# Can-Shield.net
KiCad netlist of a schematic drawn in Altium Designer
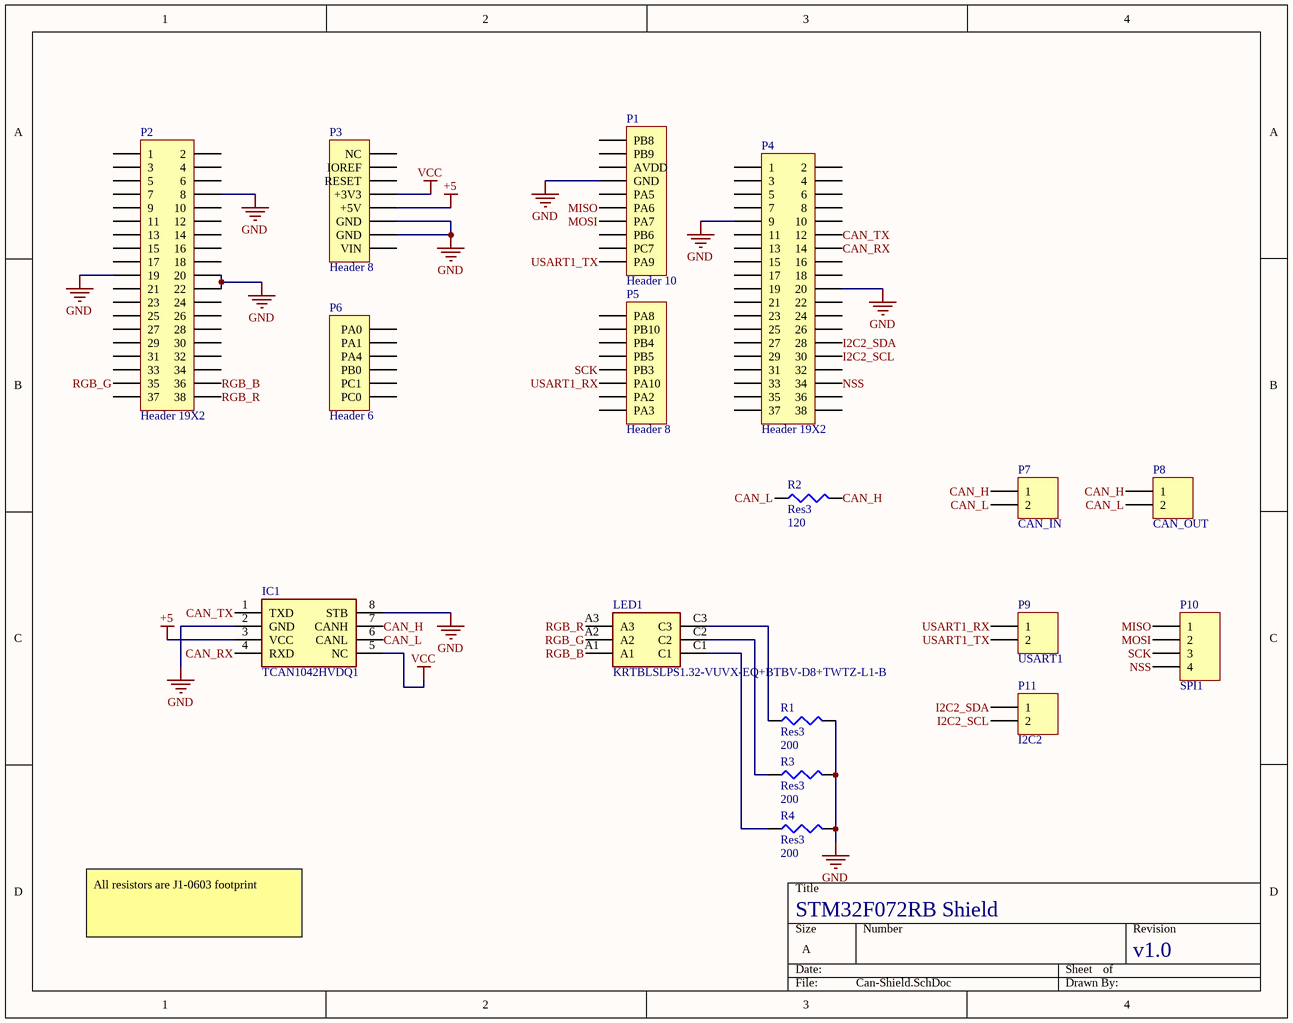
[diagram p0: Can-Shield.SchDoc]

(export (version "E")
  (design (tool "Eeschema 10.0.6"))
  (components
    (comp (ref "IC1")
      (value "TCAN1042HVDQ1")
      (footprint "SamacSys:SOIC127P600X175-8N")
      (description "Integrated Circuit")
      (fields (field (name "MOUSER PART NUMBER") "595-TCAN1042HVDQ1"))
      (libsource (lib "*") (part "TCAN1042HVDQ1"))
    )
    (comp (ref "LED1")
      (value "KRTBLSLPS1.32-VUVX-EQ+BTBV-D8+TWTZ-L1-B")
      (footprint "SamacSys:KRTBLSLPS132VUVXEQBTBVD8TWTZL1B")
      (description "LED")
      (fields (field (name "MOUSER PART NUMBER") "720-KRTBLSLPS13A0062"))
      (libsource (lib "*") (part "KRTBLSLPS1.32-VUVX-EQ+BTBV-D8+TWTZ-L1-B"))
    )
    (comp (ref "P1")
      (value "Header 10")
      (footprint "HDR1X10")
      (description "Header, 10-Pin")
      (fields (field (name "PUBLISHER") "Altium Limited"))
      (libsource (lib "Miscellaneous Connectors") (part "Header 10"))
    )
    (comp (ref "P2")
      (value "Header 19X2")
      (footprint "HDR2X19")
      (description "Header, 19-Pin, Dual row")
      (fields (field (name "PUBLISHER") "Altium Limited"))
      (libsource (lib "Miscellaneous Connectors") (part "Header 19X2"))
    )
    (comp (ref "P3")
      (value "Header 8")
      (footprint "HDR1X8")
      (description "Header, 8-Pin")
      (fields (field (name "PUBLISHER") "Altium Limited"))
      (libsource (lib "") (part "Header 8_1"))
    )
    (comp (ref "P4")
      (value "Header 19X2")
      (footprint "HDR2X19")
      (description "Header, 19-Pin, Dual row")
      (fields (field (name "PUBLISHER") "Altium Limited"))
      (libsource (lib "Miscellaneous Connectors") (part "Header 19X2"))
    )
    (comp (ref "P5")
      (value "Header 8")
      (footprint "HDR1X8")
      (description "Header, 8-Pin")
      (fields (field (name "PUBLISHER") "Altium Limited"))
      (libsource (lib "Miscellaneous Connectors") (part "Header 8"))
    )
    (comp (ref "P6")
      (value "Header 6")
      (footprint "HDR1X6")
      (description "Header, 6-Pin")
      (fields (field (name "PUBLISHER") "Altium Limited"))
      (libsource (lib "Miscellaneous Connectors") (part "Header 6"))
    )
    (comp (ref "P7")
      (value "CAN_IN")
      (footprint "HDR1X2")
      (description "Header, 2-Pin")
      (fields (field (name "PUBLISHER") "Altium Limited"))
      (libsource (lib "Miscellaneous Connectors") (part "Header 2"))
    )
    (comp (ref "P8")
      (value "CAN_OUT")
      (footprint "HDR1X2")
      (description "Header, 2-Pin")
      (fields (field (name "PUBLISHER") "Altium Limited"))
      (libsource (lib "Miscellaneous Connectors") (part "Header 2"))
    )
    (comp (ref "P9")
      (value "USART1")
      (footprint "HDR1X2")
      (description "Header, 2-Pin")
      (fields (field (name "PUBLISHER") "Altium Limited"))
      (libsource (lib "Miscellaneous Connectors") (part "Header 2"))
    )
    (comp (ref "P10")
      (value "SPI1")
      (footprint "HDR1X4")
      (description "Header, 4-Pin")
      (fields (field (name "PUBLISHER") "Altium Limited"))
      (libsource (lib "Miscellaneous Connectors") (part "Header 4"))
    )
    (comp (ref "P11")
      (value "I2C2")
      (footprint "HDR1X2")
      (description "Header, 2-Pin")
      (fields (field (name "PUBLISHER") "Altium Limited"))
      (libsource (lib "Miscellaneous Connectors") (part "Header 2"))
    )
    (comp (ref "R1")
      (value "Res3")
      (footprint "J1-0603")
      (description "Resistor")
      (fields (field (name "ALTIUM_VALUE") "200") (field (name "PUBLISHER") "Altium Limited"))
      (libsource (lib "Miscellaneous Devices") (part "Res3"))
    )
    (comp (ref "R2")
      (value "Res3")
      (footprint "J1-0603")
      (description "Resistor")
      (fields (field (name "ALTIUM_VALUE") "120") (field (name "PUBLISHER") "Altium Limited"))
      (libsource (lib "Miscellaneous Devices") (part "Res3"))
    )
    (comp (ref "R3")
      (value "Res3")
      (footprint "J1-0603")
      (description "Resistor")
      (fields (field (name "ALTIUM_VALUE") "200") (field (name "PUBLISHER") "Altium Limited"))
      (libsource (lib "Miscellaneous Devices") (part "Res3"))
    )
    (comp (ref "R4")
      (value "Res3")
      (footprint "J1-0603")
      (description "Resistor")
      (fields (field (name "ALTIUM_VALUE") "200") (field (name "PUBLISHER") "Altium Limited"))
      (libsource (lib "Miscellaneous Devices") (part "Res3"))
    )
  )
  (nets
    (net (code "1") (name "+5") (class "Default")
      (node (ref "IC1") (pin "3") (pinfunction "VCC_3") (pintype "passive"))
      (node (ref "P3") (pin "5") (pinfunction "+5V_5") (pintype "passive"))
    )
    (net (code "2") (name "/CAN_H") (class "Default")
      (node (ref "IC1") (pin "7") (pinfunction "CANH_7") (pintype "passive"))
      (node (ref "P7") (pin "1") (pinfunction "1_1") (pintype "passive"))
      (node (ref "P8") (pin "1") (pinfunction "1_1") (pintype "passive"))
      (node (ref "R2") (pin "2") (pinfunction "2_2") (pintype "passive"))
    )
    (net (code "3") (name "/CAN_L") (class "Default")
      (node (ref "IC1") (pin "6") (pinfunction "CANL_6") (pintype "passive"))
      (node (ref "P7") (pin "2") (pinfunction "2_2") (pintype "passive"))
      (node (ref "P8") (pin "2") (pinfunction "2_2") (pintype "passive"))
      (node (ref "R2") (pin "1") (pinfunction "1_1") (pintype "passive"))
    )
    (net (code "4") (name "/CAN_RX") (class "Default")
      (node (ref "IC1") (pin "4") (pinfunction "RXD_4") (pintype "passive"))
      (node (ref "P4") (pin "14") (pinfunction "14_14") (pintype "passive"))
    )
    (net (code "5") (name "/CAN_TX") (class "Default")
      (node (ref "IC1") (pin "1") (pinfunction "TXD_1") (pintype "passive"))
      (node (ref "P4") (pin "12") (pinfunction "12_12") (pintype "passive"))
    )
    (net (code "6") (name "/I2C2_SCL") (class "Default")
      (node (ref "P11") (pin "2") (pinfunction "2_2") (pintype "passive"))
      (node (ref "P4") (pin "30") (pinfunction "30_30") (pintype "passive"))
    )
    (net (code "7") (name "/I2C2_SDA") (class "Default")
      (node (ref "P11") (pin "1") (pinfunction "1_1") (pintype "passive"))
      (node (ref "P4") (pin "28") (pinfunction "28_28") (pintype "passive"))
    )
    (net (code "8") (name "/MISO") (class "Default")
      (node (ref "P1") (pin "6") (pinfunction "PA6_6") (pintype "passive"))
      (node (ref "P10") (pin "1") (pinfunction "1_1") (pintype "passive"))
    )
    (net (code "9") (name "/MOSI") (class "Default")
      (node (ref "P1") (pin "7") (pinfunction "PA7_7") (pintype "passive"))
      (node (ref "P10") (pin "2") (pinfunction "2_2") (pintype "passive"))
    )
    (net (code "10") (name "/NSS") (class "Default")
      (node (ref "P10") (pin "4") (pinfunction "4_4") (pintype "passive"))
      (node (ref "P4") (pin "34") (pinfunction "34_34") (pintype "passive"))
    )
    (net (code "11") (name "/RGB_B") (class "Default")
      (node (ref "LED1") (pin "A1") (pinfunction "A1_A1") (pintype "passive"))
      (node (ref "P2") (pin "36") (pinfunction "36_36") (pintype "passive"))
    )
    (net (code "12") (name "/RGB_G") (class "Default")
      (node (ref "LED1") (pin "A2") (pinfunction "A2_A2") (pintype "passive"))
      (node (ref "P2") (pin "35") (pinfunction "35_35") (pintype "passive"))
    )
    (net (code "13") (name "/RGB_R") (class "Default")
      (node (ref "LED1") (pin "A3") (pinfunction "A3_A3") (pintype "passive"))
      (node (ref "P2") (pin "38") (pinfunction "38_38") (pintype "passive"))
    )
    (net (code "14") (name "/SCK") (class "Default")
      (node (ref "P10") (pin "3") (pinfunction "3_3") (pintype "passive"))
      (node (ref "P5") (pin "5") (pinfunction "PB3_5") (pintype "passive"))
    )
    (net (code "15") (name "/USART1_RX") (class "Default")
      (node (ref "P5") (pin "6") (pinfunction "PA10_6") (pintype "passive"))
      (node (ref "P9") (pin "1") (pinfunction "1_1") (pintype "passive"))
    )
    (net (code "16") (name "/USART1_TX") (class "Default")
      (node (ref "P1") (pin "10") (pinfunction "PA9_10") (pintype "passive"))
      (node (ref "P9") (pin "2") (pinfunction "2_2") (pintype "passive"))
    )
    (net (code "17") (name "GND") (class "Default")
      (node (ref "IC1") (pin "2") (pinfunction "GND_2") (pintype "passive"))
      (node (ref "IC1") (pin "8") (pinfunction "STB_8") (pintype "passive"))
      (node (ref "P1") (pin "4") (pinfunction "GND_4") (pintype "passive"))
      (node (ref "P2") (pin "19") (pinfunction "19_19") (pintype "passive"))
      (node (ref "P2") (pin "20") (pinfunction "20_20") (pintype "passive"))
      (node (ref "P2") (pin "22") (pinfunction "22_22") (pintype "passive"))
      (node (ref "P2") (pin "8") (pinfunction "8_8") (pintype "passive"))
      (node (ref "P3") (pin "6") (pinfunction "GND_6") (pintype "passive"))
      (node (ref "P3") (pin "7") (pinfunction "GND_7") (pintype "passive"))
      (node (ref "P4") (pin "20") (pinfunction "20_20") (pintype "passive"))
      (node (ref "P4") (pin "9") (pinfunction "9_9") (pintype "passive"))
      (node (ref "R1") (pin "2") (pinfunction "2_2") (pintype "passive"))
      (node (ref "R3") (pin "2") (pinfunction "2_2") (pintype "passive"))
      (node (ref "R4") (pin "2") (pinfunction "2_2") (pintype "passive"))
    )
    (net (code "18") (name "Net-(LED1-PadC1)") (class "Default")
      (node (ref "LED1") (pin "C1") (pinfunction "C1_C1") (pintype "passive"))
      (node (ref "R4") (pin "1") (pinfunction "1_1") (pintype "passive"))
    )
    (net (code "19") (name "Net-(LED1-PadC2)") (class "Default")
      (node (ref "LED1") (pin "C2") (pinfunction "C2_C2") (pintype "passive"))
      (node (ref "R3") (pin "1") (pinfunction "1_1") (pintype "passive"))
    )
    (net (code "20") (name "Net-(LED1-PadC3)") (class "Default")
      (node (ref "LED1") (pin "C3") (pinfunction "C3_C3") (pintype "passive"))
      (node (ref "R1") (pin "1") (pinfunction "1_1") (pintype "passive"))
    )
    (net (code "21") (name "VCC") (class "Default")
      (node (ref "IC1") (pin "5") (pinfunction "NC_5") (pintype "passive"))
      (node (ref "P3") (pin "4") (pinfunction "+3V3_4") (pintype "passive"))
    )
    (net (code "22") (name "unconnected-(P1-AVDD-Pad3)") (class "Default")
      (node (ref "P1") (pin "3") (pinfunction "AVDD_3") (pintype "passive"))
    )
    (net (code "23") (name "unconnected-(P1-PA5-Pad5)") (class "Default")
      (node (ref "P1") (pin "5") (pinfunction "PA5_5") (pintype "passive"))
    )
    (net (code "24") (name "unconnected-(P1-PB6-Pad8)") (class "Default")
      (node (ref "P1") (pin "8") (pinfunction "PB6_8") (pintype "passive"))
    )
    (net (code "25") (name "unconnected-(P1-PB8-Pad1)") (class "Default")
      (node (ref "P1") (pin "1") (pinfunction "PB8_1") (pintype "passive"))
    )
    (net (code "26") (name "unconnected-(P1-PB9-Pad2)") (class "Default")
      (node (ref "P1") (pin "2") (pinfunction "PB9_2") (pintype "passive"))
    )
    (net (code "27") (name "unconnected-(P1-PC7-Pad9)") (class "Default")
      (node (ref "P1") (pin "9") (pinfunction "PC7_9") (pintype "passive"))
    )
    (net (code "28") (name "unconnected-(P2-Pad1)") (class "Default")
      (node (ref "P2") (pin "1") (pinfunction "1_1") (pintype "passive"))
    )
    (net (code "29") (name "unconnected-(P2-Pad2)") (class "Default")
      (node (ref "P2") (pin "2") (pinfunction "2_2") (pintype "passive"))
    )
    (net (code "30") (name "unconnected-(P2-Pad3)") (class "Default")
      (node (ref "P2") (pin "3") (pinfunction "3_3") (pintype "passive"))
    )
    (net (code "31") (name "unconnected-(P2-Pad4)") (class "Default")
      (node (ref "P2") (pin "4") (pinfunction "4_4") (pintype "passive"))
    )
    (net (code "32") (name "unconnected-(P2-Pad5)") (class "Default")
      (node (ref "P2") (pin "5") (pinfunction "5_5") (pintype "passive"))
    )
    (net (code "33") (name "unconnected-(P2-Pad6)") (class "Default")
      (node (ref "P2") (pin "6") (pinfunction "6_6") (pintype "passive"))
    )
    (net (code "34") (name "unconnected-(P2-Pad7)") (class "Default")
      (node (ref "P2") (pin "7") (pinfunction "7_7") (pintype "passive"))
    )
    (net (code "35") (name "unconnected-(P2-Pad9)") (class "Default")
      (node (ref "P2") (pin "9") (pinfunction "9_9") (pintype "passive"))
    )
    (net (code "36") (name "unconnected-(P2-Pad10)") (class "Default")
      (node (ref "P2") (pin "10") (pinfunction "10_10") (pintype "passive"))
    )
    (net (code "37") (name "unconnected-(P2-Pad11)") (class "Default")
      (node (ref "P2") (pin "11") (pinfunction "11_11") (pintype "passive"))
    )
    (net (code "38") (name "unconnected-(P2-Pad12)") (class "Default")
      (node (ref "P2") (pin "12") (pinfunction "12_12") (pintype "passive"))
    )
    (net (code "39") (name "unconnected-(P2-Pad13)") (class "Default")
      (node (ref "P2") (pin "13") (pinfunction "13_13") (pintype "passive"))
    )
    (net (code "40") (name "unconnected-(P2-Pad14)") (class "Default")
      (node (ref "P2") (pin "14") (pinfunction "14_14") (pintype "passive"))
    )
    (net (code "41") (name "unconnected-(P2-Pad15)") (class "Default")
      (node (ref "P2") (pin "15") (pinfunction "15_15") (pintype "passive"))
    )
    (net (code "42") (name "unconnected-(P2-Pad16)") (class "Default")
      (node (ref "P2") (pin "16") (pinfunction "16_16") (pintype "passive"))
    )
    (net (code "43") (name "unconnected-(P2-Pad17)") (class "Default")
      (node (ref "P2") (pin "17") (pinfunction "17_17") (pintype "passive"))
    )
    (net (code "44") (name "unconnected-(P2-Pad18)") (class "Default")
      (node (ref "P2") (pin "18") (pinfunction "18_18") (pintype "passive"))
    )
    (net (code "45") (name "unconnected-(P2-Pad21)") (class "Default")
      (node (ref "P2") (pin "21") (pinfunction "21_21") (pintype "passive"))
    )
    (net (code "46") (name "unconnected-(P2-Pad23)") (class "Default")
      (node (ref "P2") (pin "23") (pinfunction "23_23") (pintype "passive"))
    )
    (net (code "47") (name "unconnected-(P2-Pad24)") (class "Default")
      (node (ref "P2") (pin "24") (pinfunction "24_24") (pintype "passive"))
    )
    (net (code "48") (name "unconnected-(P2-Pad25)") (class "Default")
      (node (ref "P2") (pin "25") (pinfunction "25_25") (pintype "passive"))
    )
    (net (code "49") (name "unconnected-(P2-Pad26)") (class "Default")
      (node (ref "P2") (pin "26") (pinfunction "26_26") (pintype "passive"))
    )
    (net (code "50") (name "unconnected-(P2-Pad27)") (class "Default")
      (node (ref "P2") (pin "27") (pinfunction "27_27") (pintype "passive"))
    )
    (net (code "51") (name "unconnected-(P2-Pad28)") (class "Default")
      (node (ref "P2") (pin "28") (pinfunction "28_28") (pintype "passive"))
    )
    (net (code "52") (name "unconnected-(P2-Pad29)") (class "Default")
      (node (ref "P2") (pin "29") (pinfunction "29_29") (pintype "passive"))
    )
    (net (code "53") (name "unconnected-(P2-Pad30)") (class "Default")
      (node (ref "P2") (pin "30") (pinfunction "30_30") (pintype "passive"))
    )
    (net (code "54") (name "unconnected-(P2-Pad31)") (class "Default")
      (node (ref "P2") (pin "31") (pinfunction "31_31") (pintype "passive"))
    )
    (net (code "55") (name "unconnected-(P2-Pad32)") (class "Default")
      (node (ref "P2") (pin "32") (pinfunction "32_32") (pintype "passive"))
    )
    (net (code "56") (name "unconnected-(P2-Pad33)") (class "Default")
      (node (ref "P2") (pin "33") (pinfunction "33_33") (pintype "passive"))
    )
    (net (code "57") (name "unconnected-(P2-Pad34)") (class "Default")
      (node (ref "P2") (pin "34") (pinfunction "34_34") (pintype "passive"))
    )
    (net (code "58") (name "unconnected-(P2-Pad37)") (class "Default")
      (node (ref "P2") (pin "37") (pinfunction "37_37") (pintype "passive"))
    )
    (net (code "59") (name "unconnected-(P3-IOREF-Pad2)") (class "Default")
      (node (ref "P3") (pin "2") (pinfunction "IOREF_2") (pintype "passive"))
    )
    (net (code "60") (name "unconnected-(P3-NC-Pad1)") (class "Default")
      (node (ref "P3") (pin "1") (pinfunction "NC_1") (pintype "passive"))
    )
    (net (code "61") (name "unconnected-(P3-RESET-Pad3)") (class "Default")
      (node (ref "P3") (pin "3") (pinfunction "RESET_3") (pintype "passive"))
    )
    (net (code "62") (name "unconnected-(P3-VIN-Pad8)") (class "Default")
      (node (ref "P3") (pin "8") (pinfunction "VIN_8") (pintype "passive"))
    )
    (net (code "63") (name "unconnected-(P4-Pad1)") (class "Default")
      (node (ref "P4") (pin "1") (pinfunction "1_1") (pintype "passive"))
    )
    (net (code "64") (name "unconnected-(P4-Pad2)") (class "Default")
      (node (ref "P4") (pin "2") (pinfunction "2_2") (pintype "passive"))
    )
    (net (code "65") (name "unconnected-(P4-Pad3)") (class "Default")
      (node (ref "P4") (pin "3") (pinfunction "3_3") (pintype "passive"))
    )
    (net (code "66") (name "unconnected-(P4-Pad4)") (class "Default")
      (node (ref "P4") (pin "4") (pinfunction "4_4") (pintype "passive"))
    )
    (net (code "67") (name "unconnected-(P4-Pad5)") (class "Default")
      (node (ref "P4") (pin "5") (pinfunction "5_5") (pintype "passive"))
    )
    (net (code "68") (name "unconnected-(P4-Pad6)") (class "Default")
      (node (ref "P4") (pin "6") (pinfunction "6_6") (pintype "passive"))
    )
    (net (code "69") (name "unconnected-(P4-Pad7)") (class "Default")
      (node (ref "P4") (pin "7") (pinfunction "7_7") (pintype "passive"))
    )
    (net (code "70") (name "unconnected-(P4-Pad8)") (class "Default")
      (node (ref "P4") (pin "8") (pinfunction "8_8") (pintype "passive"))
    )
    (net (code "71") (name "unconnected-(P4-Pad10)") (class "Default")
      (node (ref "P4") (pin "10") (pinfunction "10_10") (pintype "passive"))
    )
    (net (code "72") (name "unconnected-(P4-Pad11)") (class "Default")
      (node (ref "P4") (pin "11") (pinfunction "11_11") (pintype "passive"))
    )
    (net (code "73") (name "unconnected-(P4-Pad13)") (class "Default")
      (node (ref "P4") (pin "13") (pinfunction "13_13") (pintype "passive"))
    )
    (net (code "74") (name "unconnected-(P4-Pad15)") (class "Default")
      (node (ref "P4") (pin "15") (pinfunction "15_15") (pintype "passive"))
    )
    (net (code "75") (name "unconnected-(P4-Pad16)") (class "Default")
      (node (ref "P4") (pin "16") (pinfunction "16_16") (pintype "passive"))
    )
    (net (code "76") (name "unconnected-(P4-Pad17)") (class "Default")
      (node (ref "P4") (pin "17") (pinfunction "17_17") (pintype "passive"))
    )
    (net (code "77") (name "unconnected-(P4-Pad18)") (class "Default")
      (node (ref "P4") (pin "18") (pinfunction "18_18") (pintype "passive"))
    )
    (net (code "78") (name "unconnected-(P4-Pad19)") (class "Default")
      (node (ref "P4") (pin "19") (pinfunction "19_19") (pintype "passive"))
    )
    (net (code "79") (name "unconnected-(P4-Pad21)") (class "Default")
      (node (ref "P4") (pin "21") (pinfunction "21_21") (pintype "passive"))
    )
    (net (code "80") (name "unconnected-(P4-Pad22)") (class "Default")
      (node (ref "P4") (pin "22") (pinfunction "22_22") (pintype "passive"))
    )
    (net (code "81") (name "unconnected-(P4-Pad23)") (class "Default")
      (node (ref "P4") (pin "23") (pinfunction "23_23") (pintype "passive"))
    )
    (net (code "82") (name "unconnected-(P4-Pad24)") (class "Default")
      (node (ref "P4") (pin "24") (pinfunction "24_24") (pintype "passive"))
    )
    (net (code "83") (name "unconnected-(P4-Pad25)") (class "Default")
      (node (ref "P4") (pin "25") (pinfunction "25_25") (pintype "passive"))
    )
    (net (code "84") (name "unconnected-(P4-Pad26)") (class "Default")
      (node (ref "P4") (pin "26") (pinfunction "26_26") (pintype "passive"))
    )
    (net (code "85") (name "unconnected-(P4-Pad27)") (class "Default")
      (node (ref "P4") (pin "27") (pinfunction "27_27") (pintype "passive"))
    )
    (net (code "86") (name "unconnected-(P4-Pad29)") (class "Default")
      (node (ref "P4") (pin "29") (pinfunction "29_29") (pintype "passive"))
    )
    (net (code "87") (name "unconnected-(P4-Pad31)") (class "Default")
      (node (ref "P4") (pin "31") (pinfunction "31_31") (pintype "passive"))
    )
    (net (code "88") (name "unconnected-(P4-Pad32)") (class "Default")
      (node (ref "P4") (pin "32") (pinfunction "32_32") (pintype "passive"))
    )
    (net (code "89") (name "unconnected-(P4-Pad33)") (class "Default")
      (node (ref "P4") (pin "33") (pinfunction "33_33") (pintype "passive"))
    )
    (net (code "90") (name "unconnected-(P4-Pad35)") (class "Default")
      (node (ref "P4") (pin "35") (pinfunction "35_35") (pintype "passive"))
    )
    (net (code "91") (name "unconnected-(P4-Pad36)") (class "Default")
      (node (ref "P4") (pin "36") (pinfunction "36_36") (pintype "passive"))
    )
    (net (code "92") (name "unconnected-(P4-Pad37)") (class "Default")
      (node (ref "P4") (pin "37") (pinfunction "37_37") (pintype "passive"))
    )
    (net (code "93") (name "unconnected-(P4-Pad38)") (class "Default")
      (node (ref "P4") (pin "38") (pinfunction "38_38") (pintype "passive"))
    )
    (net (code "94") (name "unconnected-(P5-PA2-Pad7)") (class "Default")
      (node (ref "P5") (pin "7") (pinfunction "PA2_7") (pintype "passive"))
    )
    (net (code "95") (name "unconnected-(P5-PA3-Pad8)") (class "Default")
      (node (ref "P5") (pin "8") (pinfunction "PA3_8") (pintype "passive"))
    )
    (net (code "96") (name "unconnected-(P5-PA8-Pad1)") (class "Default")
      (node (ref "P5") (pin "1") (pinfunction "PA8_1") (pintype "passive"))
    )
    (net (code "97") (name "unconnected-(P5-PB4-Pad3)") (class "Default")
      (node (ref "P5") (pin "3") (pinfunction "PB4_3") (pintype "passive"))
    )
    (net (code "98") (name "unconnected-(P5-PB5-Pad4)") (class "Default")
      (node (ref "P5") (pin "4") (pinfunction "PB5_4") (pintype "passive"))
    )
    (net (code "99") (name "unconnected-(P5-PB10-Pad2)") (class "Default")
      (node (ref "P5") (pin "2") (pinfunction "PB10_2") (pintype "passive"))
    )
    (net (code "100") (name "unconnected-(P6-PA0-Pad1)") (class "Default")
      (node (ref "P6") (pin "1") (pinfunction "PA0_1") (pintype "passive"))
    )
    (net (code "101") (name "unconnected-(P6-PA1-Pad2)") (class "Default")
      (node (ref "P6") (pin "2") (pinfunction "PA1_2") (pintype "passive"))
    )
    (net (code "102") (name "unconnected-(P6-PA4-Pad3)") (class "Default")
      (node (ref "P6") (pin "3") (pinfunction "PA4_3") (pintype "passive"))
    )
    (net (code "103") (name "unconnected-(P6-PB0-Pad4)") (class "Default")
      (node (ref "P6") (pin "4") (pinfunction "PB0_4") (pintype "passive"))
    )
    (net (code "104") (name "unconnected-(P6-PC0-Pad6)") (class "Default")
      (node (ref "P6") (pin "6") (pinfunction "PC0_6") (pintype "passive"))
    )
    (net (code "105") (name "unconnected-(P6-PC1-Pad5)") (class "Default")
      (node (ref "P6") (pin "5") (pinfunction "PC1_5") (pintype "passive"))
    )
  )
)
